# nrf21540_qdaa_var2.net
KiCad netlist of a schematic drawn in Altium Designer
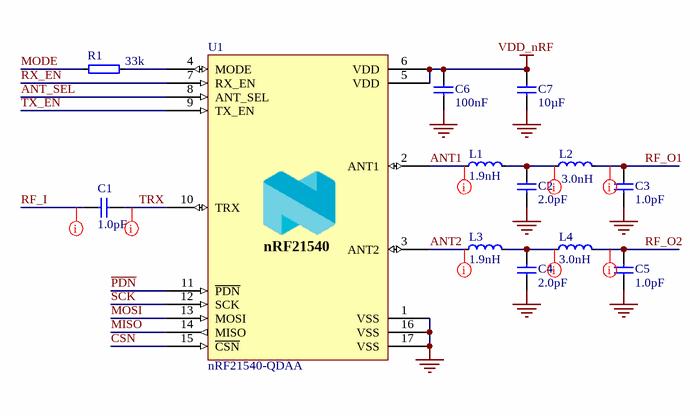
[diagram p0: nrf21540_qdaa_var2.SchDoc]

(export (version "E")
  (design (tool "Eeschema 10.0.6"))
  (components
    (comp (ref "C1")
      (value "1.0pF")
      (footprint "CAPC0603X03L_C")
      (description "Capacitor, NP0, ±0.05pF, 50V")
      (fields (field (name "PART NUMBER") "C0201-1.0p") (field (name "AUTHOR") "rsk"))
      (libsource (lib "AltiumLib") (part "CAP"))
    )
    (comp (ref "C2")
      (value "2.0pF")
      (footprint "CAPC0603X03L_C")
      (description "Capacitor, NP0, ±0.05pF, 25V")
      (fields (field (name "PART NUMBER") "C0201-2.0p-HQ-Murata") (field (name "AUTHOR") "rsk"))
      (libsource (lib "AltiumLib") (part "CAP"))
    )
    (comp (ref "C3")
      (value "1.0pF")
      (footprint "CAPC0603X03L_C")
      (description "Capacitor, NP0, ±0.05pF, 50V")
      (fields (field (name "PART NUMBER") "C0201-1.0p") (field (name "AUTHOR") "rsk"))
      (libsource (lib "AltiumLib") (part "CAP"))
    )
    (comp (ref "C4")
      (value "2.0pF")
      (footprint "CAPC0603X03L_C")
      (description "Capacitor, NP0, ±0.05pF, 25V")
      (fields (field (name "PART NUMBER") "C0201-2.0p-HQ-Murata") (field (name "AUTHOR") "rsk"))
      (libsource (lib "AltiumLib") (part "CAP"))
    )
    (comp (ref "C5")
      (value "1.0pF")
      (footprint "CAPC0603X03L_C")
      (description "Capacitor, NP0, ±0.05pF, 50V")
      (fields (field (name "PART NUMBER") "C0201-1.0p") (field (name "AUTHOR") "rsk"))
      (libsource (lib "AltiumLib") (part "CAP"))
    )
    (comp (ref "C6")
      (value "100nF")
      (footprint "CAPC0603X03L_C")
      (description "Capacitor, X5R, ±10%")
      (fields (field (name "PART NUMBER") "C0201-100n") (field (name "AUTHOR") "rsk"))
      (libsource (lib "AltiumLib") (part "CAP"))
    )
    (comp (ref "C7")
      (value "10µF")
      (footprint "CAPC1608X06L")
      (description "Capacitor, X5R, ±20%")
      (fields (field (name "PART NUMBER") "C0603-10µ") (field (name "AUTHOR") "rsk"))
      (libsource (lib "AltiumLib") (part "CAP"))
    )
    (comp (ref "L1")
      (value "1.9nH")
      (footprint "INDC0603X03L_C")
      (description "Inductor, 600mA, ±0.1ｎH, 120mOhm")
      (fields (field (name "PART NUMBER") "L0201-1n9-HQ-Murata") (field (name "AUTHOR") "rsk"))
      (libsource (lib "AltiumLib") (part "IND"))
    )
    (comp (ref "L2")
      (value "3.0nH")
      (footprint "INDC0603X03L_C")
      (description "Inductor, 600mA, ±0.1ｎH, 120mOhm")
      (fields (field (name "PART NUMBER") "L0201-3n0-HQ-Murata") (field (name "AUTHOR") "rsk"))
      (libsource (lib "AltiumLib") (part "IND"))
    )
    (comp (ref "L3")
      (value "1.9nH")
      (footprint "INDC0603X03L_C")
      (description "Inductor, 600mA, ±0.1ｎH, 120mOhm")
      (fields (field (name "PART NUMBER") "L0201-1n9-HQ-Murata") (field (name "AUTHOR") "rsk"))
      (libsource (lib "AltiumLib") (part "IND"))
    )
    (comp (ref "L4")
      (value "3.0nH")
      (footprint "INDC0603X03L_C")
      (description "Inductor, 600mA, ±0.1ｎH, 120mOhm")
      (fields (field (name "PART NUMBER") "L0201-3n0-HQ-Murata") (field (name "AUTHOR") "rsk"))
      (libsource (lib "AltiumLib") (part "IND"))
    )
    (comp (ref "R1")
      (value "33k")
      (footprint "RESC0603X03L_C")
      (description "Resistor, ±1%, 0.05W")
      (fields (field (name "PART NUMBER") "R0201-33k") (field (name "AUTHOR") "rsk"))
      (libsource (lib "AltiumLib") (part "RES"))
    )
    (comp (ref "U1")
      (value "nRF21540-QDAA")
      (footprint "QFN65P400X400X65_HS-17N")
      (description "Radio front-end / range extender for 2.4GHz")
      (fields (field (name "AUTHOR") "rsk"))
      (libsource (lib "AltiumLib") (part "nRF21540-QDAA"))
    )
  )
  (nets
    (net (code "1") (name "/ANT1") (class "Default")
      (node (ref "L1") (pin "1") (pinfunction "1_1") (pintype "passive"))
      (node (ref "U1") (pin "2") (pinfunction "ANT1_2") (pintype "bidirectional"))
    )
    (net (code "2") (name "/ANT2") (class "Default")
      (node (ref "L3") (pin "1") (pinfunction "1_1") (pintype "passive"))
      (node (ref "U1") (pin "3") (pinfunction "ANT2_3") (pintype "bidirectional"))
    )
    (net (code "3") (name "/ANT_SEL") (class "Default")
      (node (ref "U1") (pin "8") (pinfunction "ANT_SEL_8") (pintype "input"))
    )
    (net (code "4") (name "/MISO") (class "Default")
      (node (ref "U1") (pin "14") (pinfunction "MISO_14") (pintype "output"))
    )
    (net (code "5") (name "/MODE") (class "Default")
      (node (ref "R1") (pin "1") (pinfunction "1_1") (pintype "passive"))
    )
    (net (code "6") (name "/MOSI") (class "Default")
      (node (ref "U1") (pin "13") (pinfunction "MOSI_13") (pintype "input"))
    )
    (net (code "7") (name "/RF_I") (class "Default")
      (node (ref "C1") (pin "1") (pinfunction "1_1") (pintype "passive"))
    )
    (net (code "8") (name "/RF_O1") (class "Default")
      (node (ref "C3") (pin "2") (pinfunction "2_2") (pintype "passive"))
      (node (ref "L2") (pin "2") (pinfunction "2_2") (pintype "passive"))
    )
    (net (code "9") (name "/RF_O2") (class "Default")
      (node (ref "C5") (pin "2") (pinfunction "2_2") (pintype "passive"))
      (node (ref "L4") (pin "2") (pinfunction "2_2") (pintype "passive"))
    )
    (net (code "10") (name "/RX_EN") (class "Default")
      (node (ref "U1") (pin "7") (pinfunction "RX_EN_7") (pintype "input"))
    )
    (net (code "11") (name "/SCK") (class "Default")
      (node (ref "U1") (pin "12") (pinfunction "SCK_12") (pintype "input"))
    )
    (net (code "12") (name "/TRX") (class "Default")
      (node (ref "C1") (pin "2") (pinfunction "2_2") (pintype "passive"))
      (node (ref "U1") (pin "10") (pinfunction "TRX_10") (pintype "bidirectional"))
    )
    (net (code "13") (name "/TX_EN") (class "Default")
      (node (ref "U1") (pin "9") (pinfunction "TX_EN_9") (pintype "input"))
    )
    (net (code "14") (name "/~{CSN}") (class "Default")
      (node (ref "U1") (pin "15") (pinfunction "~{CSN}_15") (pintype "input"))
    )
    (net (code "15") (name "/~{PDN}") (class "Default")
      (node (ref "U1") (pin "11") (pinfunction "~{PDN}_11") (pintype "input"))
    )
    (net (code "16") (name "GND") (class "Default")
      (node (ref "C2") (pin "1") (pinfunction "1_1") (pintype "passive"))
      (node (ref "C3") (pin "1") (pinfunction "1_1") (pintype "passive"))
      (node (ref "C4") (pin "1") (pinfunction "1_1") (pintype "passive"))
      (node (ref "C5") (pin "1") (pinfunction "1_1") (pintype "passive"))
      (node (ref "C6") (pin "1") (pinfunction "1_1") (pintype "passive"))
      (node (ref "C7") (pin "1") (pinfunction "1_1") (pintype "passive"))
      (node (ref "U1") (pin "1") (pinfunction "VSS_1") (pintype "power_in"))
      (node (ref "U1") (pin "16") (pinfunction "VSS_16") (pintype "power_in"))
      (node (ref "U1") (pin "17") (pinfunction "VSS_17") (pintype "power_in"))
    )
    (net (code "17") (name "Net-(C2-Pad2)") (class "Default")
      (node (ref "C2") (pin "2") (pinfunction "2_2") (pintype "passive"))
      (node (ref "L1") (pin "2") (pinfunction "2_2") (pintype "passive"))
      (node (ref "L2") (pin "1") (pinfunction "1_1") (pintype "passive"))
    )
    (net (code "18") (name "Net-(C4-Pad2)") (class "Default")
      (node (ref "C4") (pin "2") (pinfunction "2_2") (pintype "passive"))
      (node (ref "L3") (pin "2") (pinfunction "2_2") (pintype "passive"))
      (node (ref "L4") (pin "1") (pinfunction "1_1") (pintype "passive"))
    )
    (net (code "19") (name "Net-(U1-MODE)") (class "Default")
      (node (ref "R1") (pin "2") (pinfunction "2_2") (pintype "passive"))
      (node (ref "U1") (pin "4") (pinfunction "MODE_4") (pintype "bidirectional"))
    )
    (net (code "20") (name "VDD_nRF") (class "Default")
      (node (ref "C6") (pin "2") (pinfunction "2_2") (pintype "passive"))
      (node (ref "C7") (pin "2") (pinfunction "2_2") (pintype "passive"))
      (node (ref "U1") (pin "5") (pinfunction "VDD_5") (pintype "power_in"))
      (node (ref "U1") (pin "6") (pinfunction "VDD_6") (pintype "power_in"))
    )
  )
)
